# i2c_master_v2.net
KiCad netlist of a schematic drawn in EAGLE
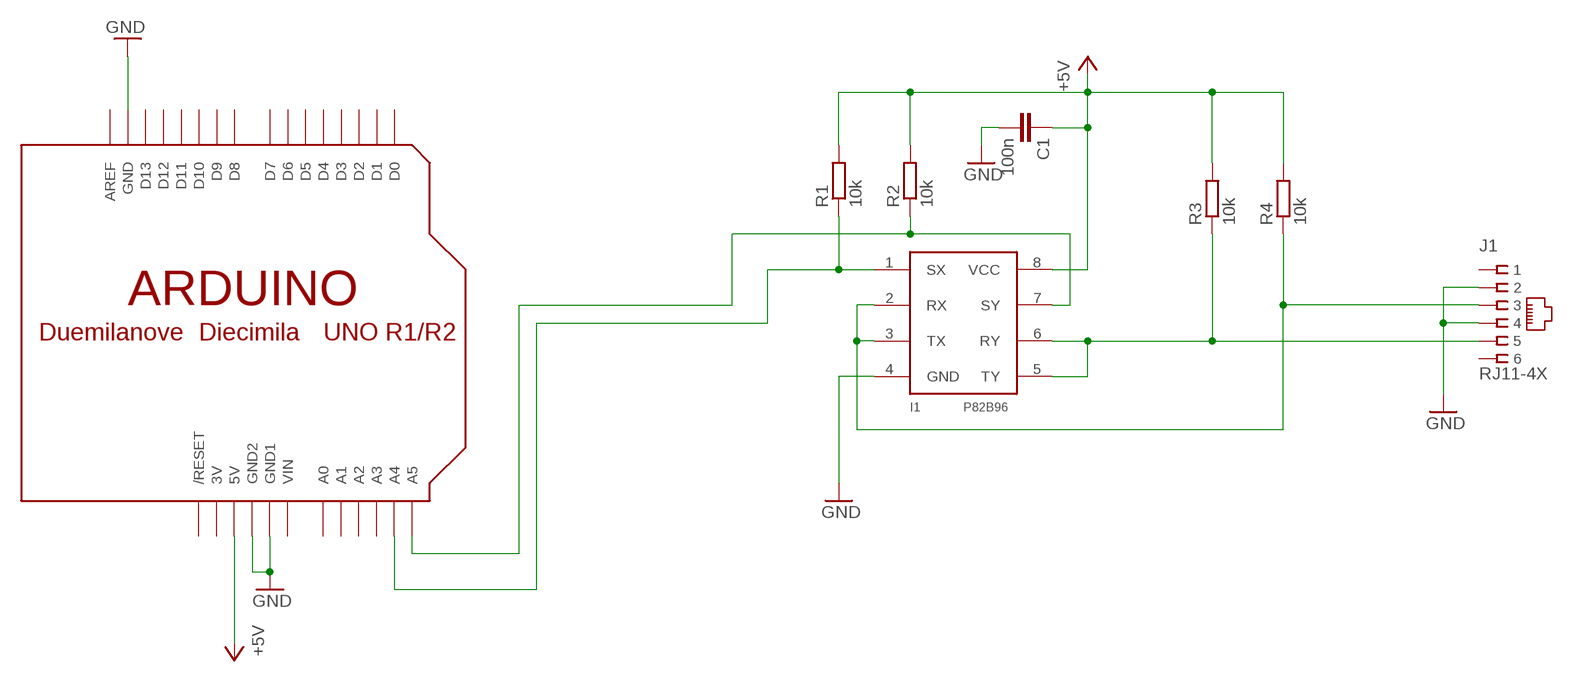
[diagram p0: schematic, sheet 1]

(export (version "E")
  (design (tool "Eeschema 10.0.6"))
  (components
    (comp (ref "C1")
      (value "100n")
      (footprint "eagle-import:C1206")
      (libsource (lib "eagle-import") (part "C-EUC1206"))
    )
    (comp (ref "I1")
      (value "P82B96")
      (footprint "eagle-import:SOIC8")
      (libsource (lib "eagle-import") (part "P82B96"))
    )
    (comp (ref "J1")
      (value "RJ11-4X")
      (footprint "eagle-import:RJ11-NO_SHIELD")
      (fields (field (name "MPN") "6609214-3"))
      (libsource (lib "eagle-import") (part "RJ11-4X"))
    )
    (comp (ref "R1")
      (value "10k")
      (footprint "eagle-import:M1206")
      (libsource (lib "eagle-import") (part "R-EU_M1206"))
    )
    (comp (ref "R2")
      (value "10k")
      (footprint "eagle-import:M1206")
      (libsource (lib "eagle-import") (part "R-EU_M1206"))
    )
    (comp (ref "R3")
      (value "10k")
      (footprint "eagle-import:M1206")
      (libsource (lib "eagle-import") (part "R-EU_M1206"))
    )
    (comp (ref "R4")
      (value "10k")
      (footprint "eagle-import:M1206")
      (libsource (lib "eagle-import") (part "R-EU_M1206"))
    )
    (comp (ref "U$1")
      (value "ARDUINO-NOHOLE")
      (footprint "eagle-import:ARDUINO-NOHOLE")
      (libsource (lib "eagle-import") (part "ARDUINO-NOHOLE"))
    )
  )
  (nets
    (net (code "1") (name "+5V") (class "Default")
      (node (ref "C1") (pin "1") (pinfunction "1_1") (pintype "passive"))
      (node (ref "I1") (pin "8") (pinfunction "VCC_8") (pintype "bidirectional"))
      (node (ref "R1") (pin "2") (pinfunction "2_2") (pintype "passive"))
      (node (ref "R2") (pin "2") (pinfunction "2_2") (pintype "passive"))
      (node (ref "R3") (pin "2") (pinfunction "2_2") (pintype "passive"))
      (node (ref "R4") (pin "2") (pinfunction "2_2") (pintype "passive"))
      (node (ref "U$1") (pin "5V") (pinfunction "5V_5V") (pintype "power_in"))
    )
    (net (code "2") (name "/3V") (class "Default")
      (node (ref "U$1") (pin "3V") (pinfunction "3V_3V") (pintype "power_in"))
    )
    (net (code "3") (name "/VIN") (class "Default")
      (node (ref "U$1") (pin "VIN") (pinfunction "VIN_VIN") (pintype "power_in"))
    )
    (net (code "4") (name "GND") (class "Default")
      (node (ref "C1") (pin "2") (pinfunction "2_2") (pintype "passive"))
      (node (ref "I1") (pin "4") (pinfunction "GND_4") (pintype "bidirectional"))
      (node (ref "J1") (pin "2") (pinfunction "2_2") (pintype "passive"))
      (node (ref "J1") (pin "4") (pinfunction "4_4") (pintype "passive"))
      (node (ref "U$1") (pin "GND") (pinfunction "GND_GND") (pintype "power_in"))
      (node (ref "U$1") (pin "GND1") (pinfunction "GND1_GND1") (pintype "power_in"))
      (node (ref "U$1") (pin "GND2") (pinfunction "GND2_GND2") (pintype "power_in"))
    )
    (net (code "5") (name "Net-(I1-RX)") (class "Default")
      (node (ref "I1") (pin "2") (pinfunction "RX_2") (pintype "bidirectional"))
      (node (ref "I1") (pin "3") (pinfunction "TX_3") (pintype "bidirectional"))
      (node (ref "J1") (pin "3") (pinfunction "3_3") (pintype "passive"))
      (node (ref "R4") (pin "1") (pinfunction "1_1") (pintype "passive"))
    )
    (net (code "6") (name "Net-(I1-RY)") (class "Default")
      (node (ref "I1") (pin "5") (pinfunction "TY_5") (pintype "bidirectional"))
      (node (ref "I1") (pin "6") (pinfunction "RY_6") (pintype "bidirectional"))
      (node (ref "J1") (pin "5") (pinfunction "5_5") (pintype "passive"))
      (node (ref "R3") (pin "1") (pinfunction "1_1") (pintype "passive"))
    )
    (net (code "7") (name "Net-(I1-SX)") (class "Default")
      (node (ref "I1") (pin "1") (pinfunction "SX_1") (pintype "bidirectional"))
      (node (ref "R1") (pin "1") (pinfunction "1_1") (pintype "passive"))
      (node (ref "U$1") (pin "A4") (pinfunction "A4_A4") (pintype "bidirectional"))
    )
    (net (code "8") (name "Net-(I1-SY)") (class "Default")
      (node (ref "I1") (pin "7") (pinfunction "SY_7") (pintype "bidirectional"))
      (node (ref "R2") (pin "1") (pinfunction "1_1") (pintype "passive"))
      (node (ref "U$1") (pin "A5") (pinfunction "A5_A5") (pintype "bidirectional"))
    )
    (net (code "9") (name "unconnected-(J1-Pad1)") (class "Default")
      (node (ref "J1") (pin "1") (pinfunction "1_1") (pintype "passive"))
    )
    (net (code "10") (name "unconnected-(J1-Pad6)") (class "Default")
      (node (ref "J1") (pin "6") (pinfunction "6_6") (pintype "passive"))
    )
    (net (code "11") (name "unconnected-(U$1-PadA0)") (class "Default")
      (node (ref "U$1") (pin "A0") (pinfunction "A0_A0") (pintype "bidirectional"))
    )
    (net (code "12") (name "unconnected-(U$1-PadA1)") (class "Default")
      (node (ref "U$1") (pin "A1") (pinfunction "A1_A1") (pintype "bidirectional"))
    )
    (net (code "13") (name "unconnected-(U$1-PadA2)") (class "Default")
      (node (ref "U$1") (pin "A2") (pinfunction "A2_A2") (pintype "bidirectional"))
    )
    (net (code "14") (name "unconnected-(U$1-PadA3)") (class "Default")
      (node (ref "U$1") (pin "A3") (pinfunction "A3_A3") (pintype "bidirectional"))
    )
    (net (code "15") (name "unconnected-(U$1-PadAREF)") (class "Default")
      (node (ref "U$1") (pin "AREF") (pinfunction "AREF_AREF") (pintype "bidirectional"))
    )
    (net (code "16") (name "unconnected-(U$1-PadD0)") (class "Default")
      (node (ref "U$1") (pin "D0") (pinfunction "D0_D0") (pintype "bidirectional"))
    )
    (net (code "17") (name "unconnected-(U$1-PadD1)") (class "Default")
      (node (ref "U$1") (pin "D1") (pinfunction "D1_D1") (pintype "bidirectional"))
    )
    (net (code "18") (name "unconnected-(U$1-PadD2)") (class "Default")
      (node (ref "U$1") (pin "D2") (pinfunction "D2_D2") (pintype "bidirectional"))
    )
    (net (code "19") (name "unconnected-(U$1-PadD3)") (class "Default")
      (node (ref "U$1") (pin "D3") (pinfunction "D3_D3") (pintype "bidirectional"))
    )
    (net (code "20") (name "unconnected-(U$1-PadD4)") (class "Default")
      (node (ref "U$1") (pin "D4") (pinfunction "D4_D4") (pintype "bidirectional"))
    )
    (net (code "21") (name "unconnected-(U$1-PadD5)") (class "Default")
      (node (ref "U$1") (pin "D5") (pinfunction "D5_D5") (pintype "bidirectional"))
    )
    (net (code "22") (name "unconnected-(U$1-PadD6)") (class "Default")
      (node (ref "U$1") (pin "D6") (pinfunction "D6_D6") (pintype "bidirectional"))
    )
    (net (code "23") (name "unconnected-(U$1-PadD7)") (class "Default")
      (node (ref "U$1") (pin "D7") (pinfunction "D7_D7") (pintype "bidirectional"))
    )
    (net (code "24") (name "unconnected-(U$1-PadD8)") (class "Default")
      (node (ref "U$1") (pin "D8") (pinfunction "D8_D8") (pintype "bidirectional"))
    )
    (net (code "25") (name "unconnected-(U$1-PadD9)") (class "Default")
      (node (ref "U$1") (pin "D9") (pinfunction "D9_D9") (pintype "bidirectional"))
    )
    (net (code "26") (name "unconnected-(U$1-PadD10)") (class "Default")
      (node (ref "U$1") (pin "D10") (pinfunction "D10_D10") (pintype "bidirectional"))
    )
    (net (code "27") (name "unconnected-(U$1-PadD11)") (class "Default")
      (node (ref "U$1") (pin "D11") (pinfunction "D11_D11") (pintype "bidirectional"))
    )
    (net (code "28") (name "unconnected-(U$1-PadD12)") (class "Default")
      (node (ref "U$1") (pin "D12") (pinfunction "D12_D12") (pintype "bidirectional"))
    )
    (net (code "29") (name "unconnected-(U$1-PadD13)") (class "Default")
      (node (ref "U$1") (pin "D13") (pinfunction "D13_D13") (pintype "bidirectional"))
    )
    (net (code "30") (name "unconnected-(U$1-{slash}RESET-PadRESET)") (class "Default")
      (node (ref "U$1") (pin "RESET") (pinfunction "/RESET_RESET") (pintype "bidirectional"))
    )
  )
)
